# Microcontroller.net
KiCad netlist of a schematic drawn in Altium Designer
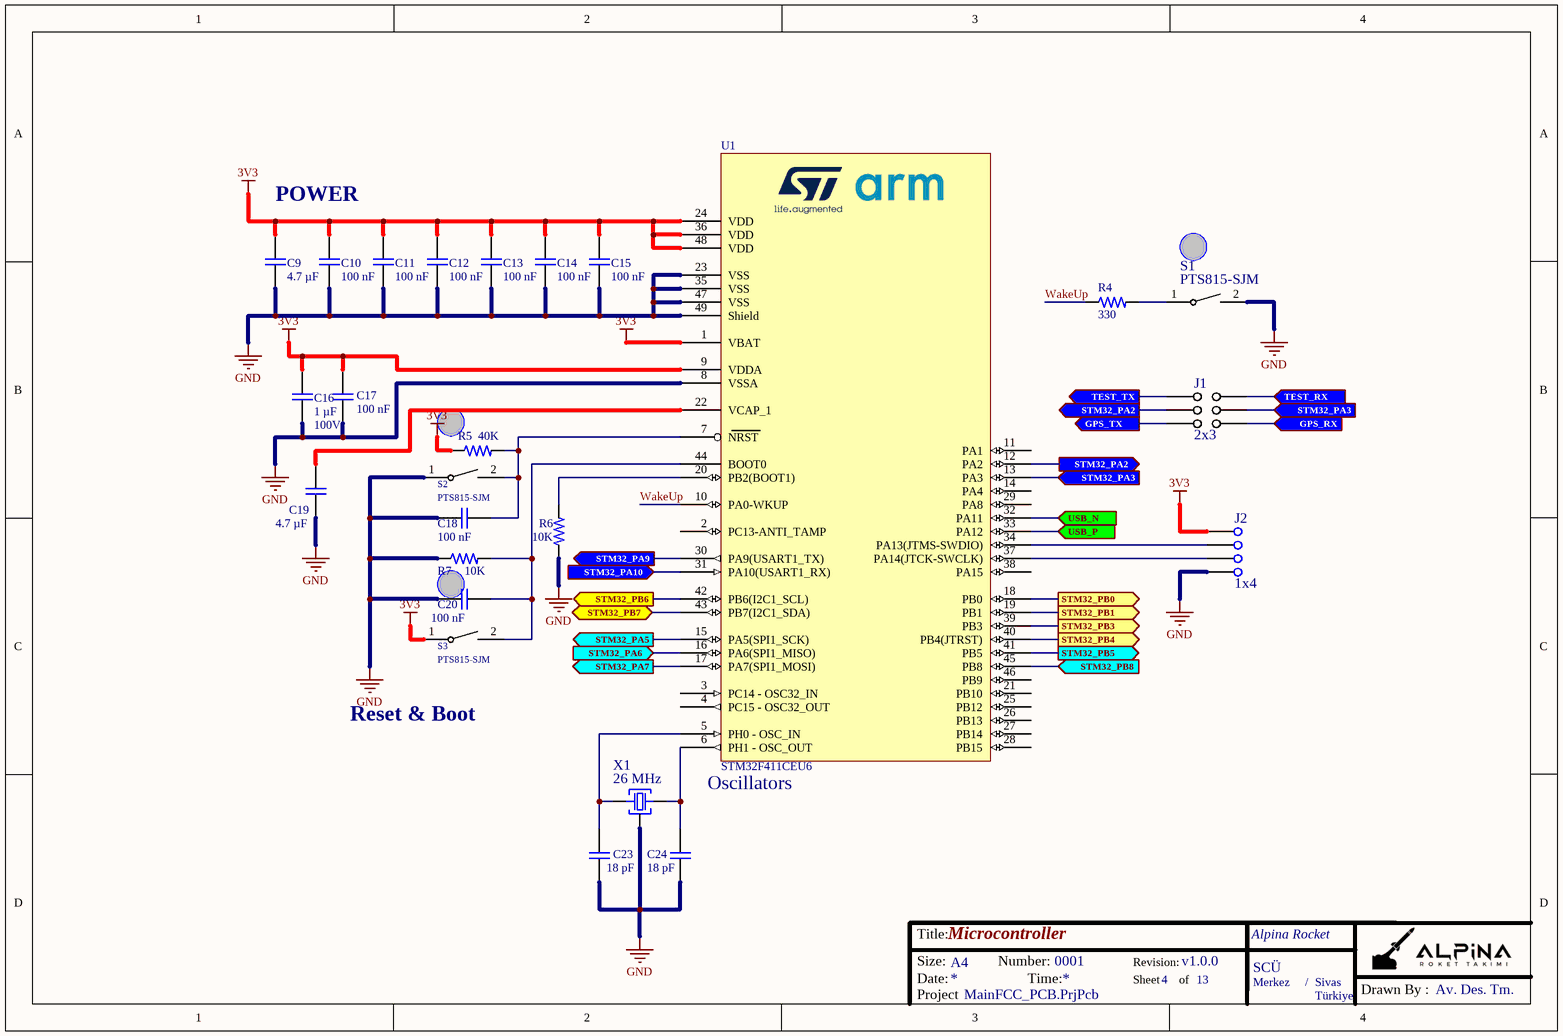
[diagram p0: Microcontroller.SchDoc]

(export (version "E")
  (design (tool "Eeschema 10.0.6"))
  (components
    (comp (ref "C9")
      (value "4.7 µF")
      (footprint "MergenElektronik_Capacitors_Ceramics_SMDs_0603_M_NS")
      (description "Mergen Elektronik - Capacitors - Ceramics - SMDs - 0603 - 4.7 µF - 16V")
      (fields (field (name "MANUFACTURER") "Samsung Electro-Mechanics") (field (name "TOLERANCE") "±10%"))
      (libsource (lib "MergenElektronik_Capacitors_Ceramics_SMDs") (part "MergenElektronik_Capacitors_Ceramic_SMDs_4.7µF_16V"))
    )
    (comp (ref "C10")
      (value "100 nF")
      (footprint "MergenElektronik_Capacitors_Ceramics_SMDs_0603_M_NS")
      (description "Mergen Elektronik - Capacitors - Ceramics - SMDs - 0603 - 100 nF - 100V")
      (fields (field (name "MANUFACTURER") "Samsung Electro-Mechanics") (field (name "TOLERANCE") "±10%"))
      (libsource (lib "MergenElektronik_Capacitors_Ceramics_SMDs") (part "MergenElektronik_Capacitors_Ceramic_SMDs_100nF_100V"))
    )
    (comp (ref "C11")
      (value "100 nF")
      (footprint "MergenElektronik_Capacitors_Ceramics_SMDs_0603_M_NS")
      (description "Mergen Elektronik - Capacitors - Ceramics - SMDs - 0603 - 100 nF - 100V")
      (fields (field (name "MANUFACTURER") "Samsung Electro-Mechanics") (field (name "TOLERANCE") "±10%"))
      (libsource (lib "MergenElektronik_Capacitors_Ceramics_SMDs") (part "MergenElektronik_Capacitors_Ceramic_SMDs_100nF_100V"))
    )
    (comp (ref "C12")
      (value "100 nF")
      (footprint "MergenElektronik_Capacitors_Ceramics_SMDs_0603_M_NS")
      (description "Mergen Elektronik - Capacitors - Ceramics - SMDs - 0603 - 100 nF - 100V")
      (fields (field (name "MANUFACTURER") "Samsung Electro-Mechanics") (field (name "TOLERANCE") "±10%"))
      (libsource (lib "MergenElektronik_Capacitors_Ceramics_SMDs") (part "MergenElektronik_Capacitors_Ceramic_SMDs_100nF_100V"))
    )
    (comp (ref "C13")
      (value "100 nF")
      (footprint "MergenElektronik_Capacitors_Ceramics_SMDs_0603_M_NS")
      (description "Mergen Elektronik - Capacitors - Ceramics - SMDs - 0603 - 100 nF - 100V")
      (fields (field (name "MANUFACTURER") "Samsung Electro-Mechanics") (field (name "TOLERANCE") "±10%"))
      (libsource (lib "MergenElektronik_Capacitors_Ceramics_SMDs") (part "MergenElektronik_Capacitors_Ceramic_SMDs_100nF_100V"))
    )
    (comp (ref "C14")
      (value "100 nF")
      (footprint "MergenElektronik_Capacitors_Ceramics_SMDs_0603_M_NS")
      (description "Mergen Elektronik - Capacitors - Ceramics - SMDs - 0603 - 100 nF - 100V")
      (fields (field (name "MANUFACTURER") "Samsung Electro-Mechanics") (field (name "TOLERANCE") "±10%"))
      (libsource (lib "MergenElektronik_Capacitors_Ceramics_SMDs") (part "MergenElektronik_Capacitors_Ceramic_SMDs_100nF_100V"))
    )
    (comp (ref "C15")
      (value "100 nF")
      (footprint "MergenElektronik_Capacitors_Ceramics_SMDs_0603_M_NS")
      (description "Mergen Elektronik - Capacitors - Ceramics - SMDs - 0603 - 100 nF - 100V")
      (fields (field (name "MANUFACTURER") "Samsung Electro-Mechanics") (field (name "TOLERANCE") "±10%"))
      (libsource (lib "MergenElektronik_Capacitors_Ceramics_SMDs") (part "MergenElektronik_Capacitors_Ceramic_SMDs_100nF_100V"))
    )
    (comp (ref "C16")
      (value "1 µF")
      (footprint "MergenElektronik_Capacitors_Ceramics_SMDs_1206_M_NS")
      (description "Mergen Elektronik - Capacitors - Ceramics - SMDs - 1206 - 1 µF - 100V")
      (fields
        (field (name "MANUFACTURER") "Samsung Electro-Mechanics")
        (field (name "TOLERANCE") "±10%")
        (field (name "VOLTAGE RATING") "100V")
      )
      (libsource (lib "MergenElektronik_Capacitors_Ceramics_SMDs") (part "MergenElektronik_Capacitors_Ceramic_SMDs_1µF_100V"))
    )
    (comp (ref "C17")
      (value "100 nF")
      (footprint "MergenElektronik_Capacitors_Ceramics_SMDs_0603_M_NS")
      (description "Mergen Elektronik - Capacitors - Ceramics - SMDs - 0603 - 100 nF - 100V")
      (fields (field (name "MANUFACTURER") "Samsung Electro-Mechanics") (field (name "TOLERANCE") "±10%"))
      (libsource (lib "MergenElektronik_Capacitors_Ceramics_SMDs") (part "MergenElektronik_Capacitors_Ceramic_SMDs_100nF_100V"))
    )
    (comp (ref "C18")
      (value "100 nF")
      (footprint "MergenElektronik_Capacitors_Ceramics_SMDs_0603_M_NS")
      (description "Mergen Elektronik - Capacitors - Ceramics - SMDs - 0603 - 100 nF - 100V")
      (fields (field (name "MANUFACTURER") "Samsung Electro-Mechanics") (field (name "TOLERANCE") "±10%"))
      (libsource (lib "MergenElektronik_Capacitors_Ceramics_SMDs") (part "MergenElektronik_Capacitors_Ceramic_SMDs_100nF_100V"))
    )
    (comp (ref "C19")
      (value "4.7 µF")
      (footprint "MergenElektronik_Capacitors_Ceramics_SMDs_0603_M_NS")
      (description "Mergen Elektronik - Capacitors - Ceramics - SMDs - 0603 - 4.7 µF - 16V")
      (fields (field (name "MANUFACTURER") "Samsung Electro-Mechanics") (field (name "TOLERANCE") "±10%"))
      (libsource (lib "MergenElektronik_Capacitors_Ceramics_SMDs") (part "MergenElektronik_Capacitors_Ceramic_SMDs_4.7µF_16V"))
    )
    (comp (ref "C20")
      (value "100 nF")
      (footprint "MergenElektronik_Capacitors_Ceramics_SMDs_0603_M_NS")
      (description "Mergen Elektronik - Capacitors - Ceramics - SMDs - 0603 - 100 nF - 100V")
      (fields (field (name "MANUFACTURER") "Samsung Electro-Mechanics") (field (name "TOLERANCE") "±10%"))
      (libsource (lib "MergenElektronik_Capacitors_Ceramics_SMDs") (part "MergenElektronik_Capacitors_Ceramic_SMDs_100nF_100V"))
    )
    (comp (ref "C23")
      (value "18 pF")
      (footprint "MergenElektronik_Capacitors_Ceramics_SMDs_0603_M_NS")
      (description "Mergen Elektronik - Capacitors - Ceramics - SMDs - 0603 - 18 pF - 50V")
      (fields (field (name "MANUFACTURER") "YAGEO") (field (name "TOLERANCE") "±5%"))
      (libsource (lib "MergenElektronik_Capacitors_Ceramics_SMDs") (part "MergenElektronik_Capacitors_Ceramic_SMDs_18pF_50V"))
    )
    (comp (ref "C24")
      (value "18 pF")
      (footprint "MergenElektronik_Capacitors_Ceramics_SMDs_0603_M_NS")
      (description "Mergen Elektronik - Capacitors - Ceramics - SMDs - 0603 - 18 pF - 50V")
      (fields (field (name "MANUFACTURER") "YAGEO") (field (name "TOLERANCE") "±5%"))
      (libsource (lib "MergenElektronik_Capacitors_Ceramics_SMDs") (part "MergenElektronik_Capacitors_Ceramic_SMDs_18pF_50V"))
    )
    (comp (ref "J1")
      (value "2x3")
      (footprint "MergenElektronik_Connectors_Headers_2x3_Male")
      (description "Mergen Elektronik - Connectors - Headers - 2x3 Male")
      (libsource (lib "MergenElektronik_Connectors_Headers") (part "MergenElektronik_Connectors_Headers_2x3_Male"))
    )
    (comp (ref "J2")
      (value "1x4")
      (footprint "MergenElektronik_Connectors_Headers_1x4_Male")
      (description "Mergen Elektronik - Connectors - Headers - 1x4 Male")
      (libsource (lib "MergenElektronik_Connectors_Headers") (part "MergenElektronik_Connectors_Headers_1x4_Male"))
    )
    (comp (ref "R4")
      (value "330")
      (footprint "MergenElektronik_Resistors_ChipResistors_0603_M_NS")
      (description "Mergen Elektronik - Resistors - Chip Resistors - 0603 - 330R")
      (fields (field (name "MANUFACTURER") "Stackpole Electronics Inc") (field (name "POWER") "1/10W"))
      (libsource (lib "MergenElektronik_Resistors_ChipResistors") (part "MergenElektronik_Resistors_ChipResistors_0603_330R"))
    )
    (comp (ref "R5")
      (value "40K")
      (footprint "MergenElektronik_Resistors_ChipResistors_0603_M_NS")
      (description "Mergen Elektronik - Resistors - Chip Resistors - 0603 - 40K")
      (fields (field (name "MANUFACTURER") "YAGEO") (field (name "POWER") "1/10W"))
      (libsource (lib "MergenElektronik_Resistors_ChipResistors") (part "MergenElektronik_Resistors_ChipResistors_0603_40K"))
    )
    (comp (ref "R6")
      (value "10K")
      (footprint "MergenElektronik_Resistors_ChipResistors_0603_M_NS")
      (description "Mergen Elektronik - Resistors - Chip Resistors - 0603 - 10K")
      (fields (field (name "MANUFACTURER") "Stackpole Electronics Inc") (field (name "POWER") "1/10W"))
      (libsource (lib "MergenElektronik_Resistors_ChipResistors") (part "MergenElektronik_Resistors_ChipResistors_0603_10K"))
    )
    (comp (ref "R7")
      (value "10K")
      (footprint "MergenElektronik_Resistors_ChipResistors_0603_M_NS")
      (description "Mergen Elektronik - Resistors - Chip Resistors - 0603 - 10K")
      (fields (field (name "MANUFACTURER") "Stackpole Electronics Inc") (field (name "POWER") "1/10W"))
      (libsource (lib "MergenElektronik_Resistors_ChipResistors") (part "MergenElektronik_Resistors_ChipResistors_0603_10K"))
    )
    (comp (ref "S1")
      (value "PTS815-SJM")
      (footprint "MergenElektronik_Switches_TactileSwitches_PTS815")
      (description "Mergen Elektronik - Switches - Tactile  Switches")
      (fields (field (name "MANUFACTURER") "C&K"))
      (libsource (lib "MergenElektronik_Switches_TactileSwitches") (part "MergenElektronik_Switches_TactileSwitches_PTS815-SJM"))
    )
    (comp (ref "S2")
      (value "PTS815-SJM")
      (footprint "MergenElektronik_Switches_TactileSwitches_PTS815")
      (description "Mergen Elektronik - Switches - Tactile  Switches")
      (fields (field (name "MANUFACTURER") "C&K"))
      (libsource (lib "MergenElektronik_Switches_TactileSwitches") (part "MergenElektronik_Switches_TactileSwitches_PTS815-SJM"))
    )
    (comp (ref "S3")
      (value "PTS815-SJM")
      (footprint "MergenElektronik_Switches_TactileSwitches_PTS815")
      (description "Mergen Elektronik - Switches - Tactile  Switches")
      (fields (field (name "MANUFACTURER") "C&K"))
      (libsource (lib "MergenElektronik_Switches_TactileSwitches") (part "MergenElektronik_Switches_TactileSwitches_PTS815-SJM"))
    )
    (comp (ref "U1")
      (value "STM32F411CEU6")
      (footprint "MergenElektronik_Microcontrollers_STMicroelectronics_UFQFPN-48")
      (description "Mergen Elektronik - Microcontrollers - STMicroelectronics - STM32F411CEU6")
      (fields (field (name "MANUFACTURER") "STMicroelectronics"))
      (libsource (lib "MergenElektronik_Microcontrollers_STMicroelectronics") (part "MergenElektronik_Microcontrollers_STMicroelectronics_STM32F411CEU6"))
    )
    (comp (ref "X1")
      (value "26 MHz")
      (footprint "MergenElektronik_Oscillators_Crystals_4-SMD")
      (description "Mergen Elektronik - Oscilators - Crystals - 4-SMD - 26 MHz")
      (fields (field (name "MANUFACTURER") "TXC CORPORATION"))
      (libsource (lib "MergenElektronik_Oscillators_Crystals") (part "MergenElektronik_Oscillators_Crystals_4_SMD_26MHz"))
    )
  )
  (nets
    (net (code "1") (name "/GPS_RX") (class "Default")
      (node (ref "J1") (pin "4") (pinfunction "4_4") (pintype "passive"))
    )
    (net (code "2") (name "/GPS_TX") (class "Default")
      (node (ref "J1") (pin "1") (pinfunction "1_1") (pintype "passive"))
    )
    (net (code "3") (name "/STM32_PA2") (class "Default")
      (node (ref "J1") (pin "2") (pinfunction "2_2") (pintype "passive"))
      (node (ref "U1") (pin "12") (pinfunction "PA2_12") (pintype "bidirectional"))
    )
    (net (code "4") (name "/STM32_PA3") (class "Default")
      (node (ref "J1") (pin "5") (pinfunction "5_5") (pintype "passive"))
      (node (ref "U1") (pin "13") (pinfunction "PA3_13") (pintype "bidirectional"))
    )
    (net (code "5") (name "/STM32_PA5") (class "Default")
      (node (ref "U1") (pin "15") (pinfunction "PA5(SPI1_SCK)_15") (pintype "bidirectional"))
    )
    (net (code "6") (name "/STM32_PA6") (class "Default")
      (node (ref "U1") (pin "16") (pinfunction "PA6(SPI1_MISO)_16") (pintype "bidirectional"))
    )
    (net (code "7") (name "/STM32_PA7") (class "Default")
      (node (ref "U1") (pin "17") (pinfunction "PA7(SPI1_MOSI)_17") (pintype "bidirectional"))
    )
    (net (code "8") (name "/STM32_PA9") (class "Default")
      (node (ref "U1") (pin "30") (pinfunction "PA9(USART1_TX)_30") (pintype "output"))
    )
    (net (code "9") (name "/STM32_PA10") (class "Default")
      (node (ref "U1") (pin "31") (pinfunction "PA10(USART1_RX)_31") (pintype "input"))
    )
    (net (code "10") (name "/STM32_PB0") (class "Default")
      (node (ref "U1") (pin "18") (pinfunction "PB0_18") (pintype "bidirectional"))
    )
    (net (code "11") (name "/STM32_PB1") (class "Default")
      (node (ref "U1") (pin "19") (pinfunction "PB1_19") (pintype "bidirectional"))
    )
    (net (code "12") (name "/STM32_PB3") (class "Default")
      (node (ref "U1") (pin "39") (pinfunction "PB3_39") (pintype "bidirectional"))
    )
    (net (code "13") (name "/STM32_PB4") (class "Default")
      (node (ref "U1") (pin "40") (pinfunction "PB4(JTRST)_40") (pintype "bidirectional"))
    )
    (net (code "14") (name "/STM32_PB5") (class "Default")
      (node (ref "U1") (pin "41") (pinfunction "PB5_41") (pintype "bidirectional"))
    )
    (net (code "15") (name "/STM32_PB6") (class "Default")
      (node (ref "U1") (pin "42") (pinfunction "PB6(I2C1_SCL)_42") (pintype "bidirectional"))
    )
    (net (code "16") (name "/STM32_PB7") (class "Default")
      (node (ref "U1") (pin "43") (pinfunction "PB7(I2C1_SDA)_43") (pintype "bidirectional"))
    )
    (net (code "17") (name "/STM32_PB8") (class "Default")
      (node (ref "U1") (pin "45") (pinfunction "PB8_45") (pintype "bidirectional"))
    )
    (net (code "18") (name "/TEST_RX") (class "Default")
      (node (ref "J1") (pin "6") (pinfunction "6_6") (pintype "passive"))
    )
    (net (code "19") (name "/TEST_TX") (class "Default")
      (node (ref "J1") (pin "3") (pinfunction "3_3") (pintype "passive"))
    )
    (net (code "20") (name "/USB_N") (class "Default")
      (node (ref "U1") (pin "32") (pinfunction "PA11_32") (pintype "bidirectional"))
    )
    (net (code "21") (name "/USB_P") (class "Default")
      (node (ref "U1") (pin "33") (pinfunction "PA12_33") (pintype "bidirectional"))
    )
    (net (code "22") (name "/WakeUp") (class "Default")
      (node (ref "R4") (pin "1") (pinfunction "1_1") (pintype "passive"))
      (node (ref "U1") (pin "10") (pinfunction "PA0-WKUP_10") (pintype "bidirectional"))
    )
    (net (code "23") (name "3V3") (class "Default")
      (node (ref "C10") (pin "1") (pinfunction "1_1") (pintype "passive"))
      (node (ref "C11") (pin "1") (pinfunction "1_1") (pintype "passive"))
      (node (ref "C12") (pin "1") (pinfunction "1_1") (pintype "passive"))
      (node (ref "C13") (pin "1") (pinfunction "1_1") (pintype "passive"))
      (node (ref "C14") (pin "1") (pinfunction "1_1") (pintype "passive"))
      (node (ref "C15") (pin "1") (pinfunction "1_1") (pintype "passive"))
      (node (ref "C16") (pin "1") (pinfunction "1_1") (pintype "passive"))
      (node (ref "C17") (pin "1") (pinfunction "1_1") (pintype "passive"))
      (node (ref "C9") (pin "1") (pinfunction "1_1") (pintype "passive"))
      (node (ref "J2") (pin "4") (pinfunction "4_4") (pintype "passive"))
      (node (ref "R5") (pin "1") (pinfunction "1_1") (pintype "passive"))
      (node (ref "S3") (pin "1") (pinfunction "1_1") (pintype "passive"))
      (node (ref "U1") (pin "1") (pinfunction "VBAT_1") (pintype "power_in"))
      (node (ref "U1") (pin "24") (pinfunction "VDD_24") (pintype "power_in"))
      (node (ref "U1") (pin "36") (pinfunction "VDD_36") (pintype "power_in"))
      (node (ref "U1") (pin "48") (pinfunction "VDD_48") (pintype "power_in"))
      (node (ref "U1") (pin "9") (pinfunction "VDDA_9") (pintype "passive"))
    )
    (net (code "24") (name "GND") (class "Default")
      (node (ref "C10") (pin "2") (pinfunction "2_2") (pintype "passive"))
      (node (ref "C11") (pin "2") (pinfunction "2_2") (pintype "passive"))
      (node (ref "C12") (pin "2") (pinfunction "2_2") (pintype "passive"))
      (node (ref "C13") (pin "2") (pinfunction "2_2") (pintype "passive"))
      (node (ref "C14") (pin "2") (pinfunction "2_2") (pintype "passive"))
      (node (ref "C15") (pin "2") (pinfunction "2_2") (pintype "passive"))
      (node (ref "C16") (pin "2") (pinfunction "2_2") (pintype "passive"))
      (node (ref "C17") (pin "2") (pinfunction "2_2") (pintype "passive"))
      (node (ref "C18") (pin "2") (pinfunction "2_2") (pintype "passive"))
      (node (ref "C19") (pin "2") (pinfunction "2_2") (pintype "passive"))
      (node (ref "C20") (pin "2") (pinfunction "2_2") (pintype "passive"))
      (node (ref "C23") (pin "2") (pinfunction "2_2") (pintype "passive"))
      (node (ref "C24") (pin "2") (pinfunction "2_2") (pintype "passive"))
      (node (ref "C9") (pin "2") (pinfunction "2_2") (pintype "passive"))
      (node (ref "J2") (pin "1") (pinfunction "1_1") (pintype "passive"))
      (node (ref "R6") (pin "1") (pinfunction "1_1") (pintype "passive"))
      (node (ref "R7") (pin "1") (pinfunction "1_1") (pintype "passive"))
      (node (ref "S1") (pin "2") (pinfunction "2_2") (pintype "passive"))
      (node (ref "S2") (pin "1") (pinfunction "1_1") (pintype "passive"))
      (node (ref "U1") (pin "23") (pinfunction "VSS_23") (pintype "power_in"))
      (node (ref "U1") (pin "35") (pinfunction "VSS_35") (pintype "power_in"))
      (node (ref "U1") (pin "47") (pinfunction "VSS_47") (pintype "power_in"))
      (node (ref "U1") (pin "49") (pinfunction "Shield_49") (pintype "passive"))
      (node (ref "U1") (pin "8") (pinfunction "VSSA_8") (pintype "passive"))
      (node (ref "X1") (pin "3") (pinfunction "3_3") (pintype "passive"))
    )
    (net (code "25") (name "Net-(R4-Pad2)") (class "Default")
      (node (ref "R4") (pin "2") (pinfunction "2_2") (pintype "passive"))
      (node (ref "S1") (pin "1") (pinfunction "1_1") (pintype "passive"))
    )
    (net (code "26") (name "Net-(U1-BOOT0)") (class "Default")
      (node (ref "C20") (pin "1") (pinfunction "1_1") (pintype "passive"))
      (node (ref "R7") (pin "2") (pinfunction "2_2") (pintype "passive"))
      (node (ref "S3") (pin "2") (pinfunction "2_2") (pintype "passive"))
      (node (ref "U1") (pin "44") (pinfunction "BOOT0_44") (pintype "passive"))
    )
    (net (code "27") (name "Net-(U1-NRST)") (class "Default")
      (node (ref "C18") (pin "1") (pinfunction "1_1") (pintype "passive"))
      (node (ref "R5") (pin "2") (pinfunction "2_2") (pintype "passive"))
      (node (ref "S2") (pin "2") (pinfunction "2_2") (pintype "passive"))
      (node (ref "U1") (pin "7") (pinfunction "NRST_7") (pintype "passive"))
    )
    (net (code "28") (name "Net-(U1-PA13(JTMS-SWDIO))") (class "Default")
      (node (ref "J2") (pin "3") (pinfunction "3_3") (pintype "passive"))
      (node (ref "U1") (pin "34") (pinfunction "PA13(JTMS-SWDIO)_34") (pintype "bidirectional"))
    )
    (net (code "29") (name "Net-(U1-PA14(JTCK-SWCLK))") (class "Default")
      (node (ref "J2") (pin "2") (pinfunction "2_2") (pintype "passive"))
      (node (ref "U1") (pin "37") (pinfunction "PA14(JTCK-SWCLK)_37") (pintype "bidirectional"))
    )
    (net (code "30") (name "Net-(U1-PB2(BOOT1))") (class "Default")
      (node (ref "R6") (pin "2") (pinfunction "2_2") (pintype "passive"))
      (node (ref "U1") (pin "20") (pinfunction "PB2(BOOT1)_20") (pintype "bidirectional"))
    )
    (net (code "31") (name "Net-(U1-PH0_-_OSC_IN)") (class "Default")
      (node (ref "C23") (pin "1") (pinfunction "1_1") (pintype "passive"))
      (node (ref "U1") (pin "5") (pinfunction "PH0_-_OSC_IN_5") (pintype "input"))
      (node (ref "X1") (pin "1") (pinfunction "1_1") (pintype "passive"))
    )
    (net (code "32") (name "Net-(U1-PH1_-_OSC_OUT)") (class "Default")
      (node (ref "C24") (pin "1") (pinfunction "1_1") (pintype "passive"))
      (node (ref "U1") (pin "6") (pinfunction "PH1_-_OSC_OUT_6") (pintype "output"))
      (node (ref "X1") (pin "2") (pinfunction "2_2") (pintype "passive"))
    )
    (net (code "33") (name "Net-(U1-VCAP_1)") (class "Default")
      (node (ref "C19") (pin "1") (pinfunction "1_1") (pintype "passive"))
      (node (ref "U1") (pin "22") (pinfunction "VCAP_1_22") (pintype "power_in"))
    )
    (net (code "34") (name "unconnected-(U1-PA1-Pad11)") (class "Default")
      (node (ref "U1") (pin "11") (pinfunction "PA1_11") (pintype "bidirectional"))
    )
    (net (code "35") (name "unconnected-(U1-PA4-Pad14)") (class "Default")
      (node (ref "U1") (pin "14") (pinfunction "PA4_14") (pintype "bidirectional"))
    )
    (net (code "36") (name "unconnected-(U1-PA8-Pad29)") (class "Default")
      (node (ref "U1") (pin "29") (pinfunction "PA8_29") (pintype "bidirectional"))
    )
    (net (code "37") (name "unconnected-(U1-PA15-Pad38)") (class "Default")
      (node (ref "U1") (pin "38") (pinfunction "PA15_38") (pintype "bidirectional"))
    )
    (net (code "38") (name "unconnected-(U1-PB9-Pad46)") (class "Default")
      (node (ref "U1") (pin "46") (pinfunction "PB9_46") (pintype "bidirectional"))
    )
    (net (code "39") (name "unconnected-(U1-PB10-Pad21)") (class "Default")
      (node (ref "U1") (pin "21") (pinfunction "PB10_21") (pintype "bidirectional"))
    )
    (net (code "40") (name "unconnected-(U1-PB12-Pad25)") (class "Default")
      (node (ref "U1") (pin "25") (pinfunction "PB12_25") (pintype "bidirectional"))
    )
    (net (code "41") (name "unconnected-(U1-PB13-Pad26)") (class "Default")
      (node (ref "U1") (pin "26") (pinfunction "PB13_26") (pintype "bidirectional"))
    )
    (net (code "42") (name "unconnected-(U1-PB14-Pad27)") (class "Default")
      (node (ref "U1") (pin "27") (pinfunction "PB14_27") (pintype "bidirectional"))
    )
    (net (code "43") (name "unconnected-(U1-PB15-Pad28)") (class "Default")
      (node (ref "U1") (pin "28") (pinfunction "PB15_28") (pintype "bidirectional"))
    )
    (net (code "44") (name "unconnected-(U1-PC13-ANTI_TAMP-Pad2)") (class "Default")
      (node (ref "U1") (pin "2") (pinfunction "PC13-ANTI_TAMP_2") (pintype "bidirectional"))
    )
    (net (code "45") (name "unconnected-(U1-PC14_-_OSC32_IN-Pad3)") (class "Default")
      (node (ref "U1") (pin "3") (pinfunction "PC14_-_OSC32_IN_3") (pintype "input"))
    )
    (net (code "46") (name "unconnected-(U1-PC15_-_OSC32_OUT-Pad4)") (class "Default")
      (node (ref "U1") (pin "4") (pinfunction "PC15_-_OSC32_OUT_4") (pintype "output"))
    )
  )
)
